# SCH_BI_PLANE__QLC_CONNECTOR_QLC260R__22_.net
KiCad netlist of a schematic drawn in EasyEDA
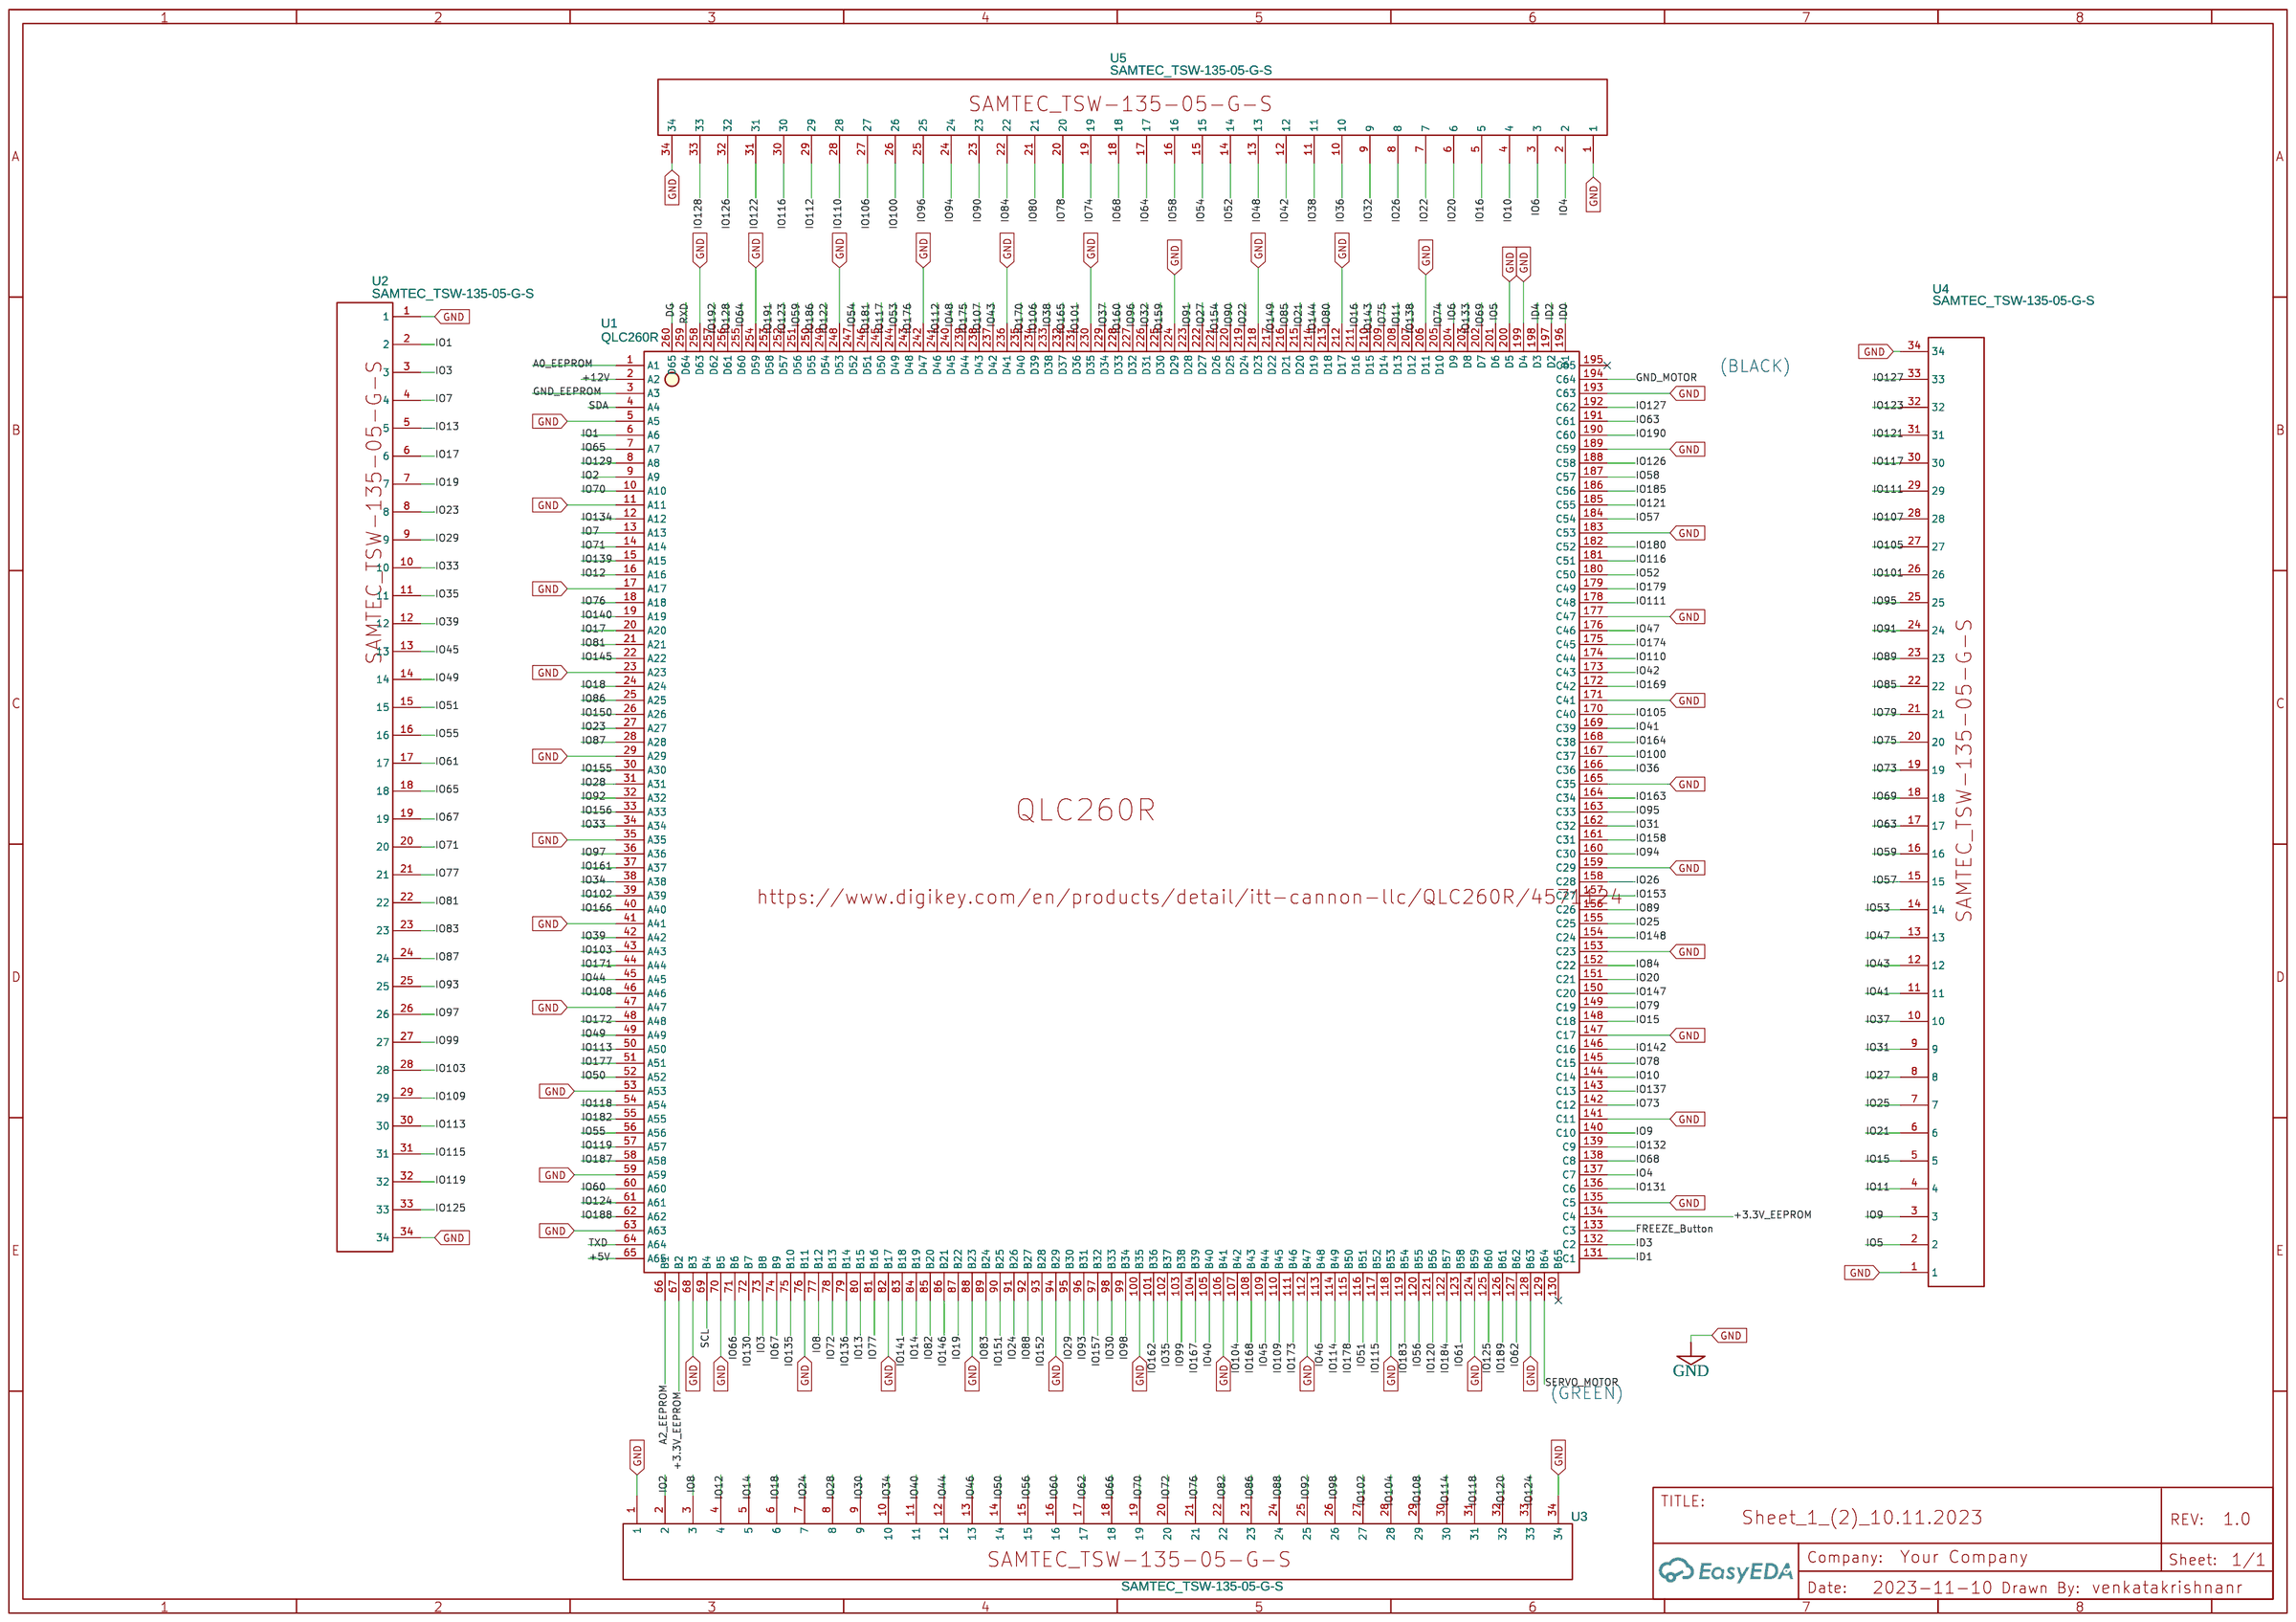
[diagram p0: schematic sheet]

(export (version "E")
  (design (tool "Eeschema 10.0.6"))
  (components
    (comp (ref "U1")
      (value "QLC260R")
      (fields (field (name "Manufacturer") "ITT Cannon, LLC"))
      (libsource (lib "") (part "QLC260R"))
    )
    (comp (ref "U2")
      (value "SAMTEC_TSW-135-05-G-S")
      (fields (field (name "Manufacturer Part") "TSW-135-05-G-S") (field (name "Manufacturer") "Samtec Inc."))
      (libsource (lib "") (part "SAMTEC_TSW-135-05-G-S_1"))
    )
    (comp (ref "U3")
      (value "SAMTEC_TSW-135-05-G-S")
      (fields (field (name "Manufacturer Part") "TSW-135-05-G-S") (field (name "Manufacturer") "Samtec Inc."))
      (libsource (lib "") (part "SAMTEC_TSW-135-05-G-S_3"))
    )
    (comp (ref "U4")
      (value "SAMTEC_TSW-135-05-G-S")
      (fields (field (name "Manufacturer Part") "TSW-135-05-G-S") (field (name "Manufacturer") "Samtec Inc."))
      (libsource (lib "") (part "SAMTEC_TSW-135-05-G-S_2"))
    )
    (comp (ref "U5")
      (value "SAMTEC_TSW-135-05-G-S")
      (fields (field (name "Manufacturer Part") "TSW-135-05-G-S") (field (name "Manufacturer") "Samtec Inc."))
      (libsource (lib "") (part "SAMTEC_TSW-135-05-G-S"))
    )
  )
  (nets
    (net (code "1") (name "/+3.3V_EEPROM") (class "Default")
      (node (ref "U1") (pin "134") (pinfunction "C4_134") (pintype "unspecified"))
      (node (ref "U1") (pin "67") (pinfunction "B2_67") (pintype "unspecified"))
    )
    (net (code "2") (name "/+5V") (class "Default")
      (node (ref "U1") (pin "65") (pinfunction "A65_65") (pintype "unspecified"))
    )
    (net (code "3") (name "/+12V") (class "Default")
      (node (ref "U1") (pin "2") (pinfunction "A2_2") (pintype "unspecified"))
    )
    (net (code "4") (name "/A0_EEPROM") (class "Default")
      (node (ref "U1") (pin "1") (pinfunction "A1_1") (pintype "unspecified"))
    )
    (net (code "5") (name "/A2_EEPROM") (class "Default")
      (node (ref "U1") (pin "66") (pinfunction "B1_66") (pintype "unspecified"))
    )
    (net (code "6") (name "/DG") (class "Default")
      (node (ref "U1") (pin "260") (pinfunction "D65_260") (pintype "unspecified"))
    )
    (net (code "7") (name "/FREEZE_Button") (class "Default")
      (node (ref "U1") (pin "133") (pinfunction "C3_133") (pintype "unspecified"))
    )
    (net (code "8") (name "/GND_EEPROM") (class "Default")
      (node (ref "U1") (pin "3") (pinfunction "A3_3") (pintype "unspecified"))
    )
    (net (code "9") (name "/GND_MOTOR") (class "Default")
      (node (ref "U1") (pin "194") (pinfunction "C64_194") (pintype "unspecified"))
    )
    (net (code "10") (name "/ID0") (class "Default")
      (node (ref "U1") (pin "196") (pinfunction "D1_196") (pintype "unspecified"))
    )
    (net (code "11") (name "/ID1") (class "Default")
      (node (ref "U1") (pin "131") (pinfunction "C1_131") (pintype "unspecified"))
    )
    (net (code "12") (name "/ID2") (class "Default")
      (node (ref "U1") (pin "197") (pinfunction "D2_197") (pintype "unspecified"))
    )
    (net (code "13") (name "/ID3") (class "Default")
      (node (ref "U1") (pin "132") (pinfunction "C2_132") (pintype "unspecified"))
    )
    (net (code "14") (name "/ID4") (class "Default")
      (node (ref "U1") (pin "198") (pinfunction "D3_198") (pintype "unspecified"))
    )
    (net (code "15") (name "/IO1") (class "Default")
      (node (ref "U1") (pin "6") (pinfunction "A6_6") (pintype "unspecified"))
      (node (ref "U2") (pin "2") (pinfunction "2_2") (pintype "unspecified"))
    )
    (net (code "16") (name "/IO2") (class "Default")
      (node (ref "U1") (pin "9") (pinfunction "A9_9") (pintype "unspecified"))
      (node (ref "U3") (pin "2") (pinfunction "2_2") (pintype "unspecified"))
    )
    (net (code "17") (name "/IO3") (class "Default")
      (node (ref "U1") (pin "73") (pinfunction "B8_73") (pintype "unspecified"))
      (node (ref "U2") (pin "3") (pinfunction "3_3") (pintype "unspecified"))
    )
    (net (code "18") (name "/IO4") (class "Default")
      (node (ref "U1") (pin "137") (pinfunction "C7_137") (pintype "unspecified"))
      (node (ref "U5") (pin "2") (pinfunction "2_2") (pintype "unspecified"))
    )
    (net (code "19") (name "/IO5") (class "Default")
      (node (ref "U1") (pin "201") (pinfunction "D6_201") (pintype "unspecified"))
      (node (ref "U4") (pin "2") (pinfunction "2_2") (pintype "unspecified"))
    )
    (net (code "20") (name "/IO6") (class "Default")
      (node (ref "U1") (pin "204") (pinfunction "D9_204") (pintype "unspecified"))
      (node (ref "U5") (pin "3") (pinfunction "3_3") (pintype "unspecified"))
    )
    (net (code "21") (name "/IO7") (class "Default")
      (node (ref "U1") (pin "13") (pinfunction "A13_13") (pintype "unspecified"))
      (node (ref "U2") (pin "4") (pinfunction "4_4") (pintype "unspecified"))
    )
    (net (code "22") (name "/IO8") (class "Default")
      (node (ref "U1") (pin "77") (pinfunction "B12_77") (pintype "unspecified"))
      (node (ref "U3") (pin "3") (pinfunction "3_3") (pintype "unspecified"))
    )
    (net (code "23") (name "/IO9") (class "Default")
      (node (ref "U1") (pin "140") (pinfunction "C10_140") (pintype "unspecified"))
      (node (ref "U4") (pin "3") (pinfunction "3_3") (pintype "unspecified"))
    )
    (net (code "24") (name "/IO10") (class "Default")
      (node (ref "U1") (pin "144") (pinfunction "C14_144") (pintype "unspecified"))
      (node (ref "U5") (pin "4") (pinfunction "4_4") (pintype "unspecified"))
    )
    (net (code "25") (name "/IO11") (class "Default")
      (node (ref "U1") (pin "208") (pinfunction "D13_208") (pintype "unspecified"))
      (node (ref "U4") (pin "4") (pinfunction "4_4") (pintype "unspecified"))
    )
    (net (code "26") (name "/IO12") (class "Default")
      (node (ref "U1") (pin "16") (pinfunction "A16_16") (pintype "unspecified"))
      (node (ref "U3") (pin "4") (pinfunction "4_4") (pintype "unspecified"))
    )
    (net (code "27") (name "/IO13") (class "Default")
      (node (ref "U1") (pin "80") (pinfunction "B15_80") (pintype "unspecified"))
      (node (ref "U2") (pin "5") (pinfunction "5_5") (pintype "unspecified"))
    )
    (net (code "28") (name "/IO14") (class "Default")
      (node (ref "U1") (pin "84") (pinfunction "B19_84") (pintype "unspecified"))
      (node (ref "U3") (pin "5") (pinfunction "5_5") (pintype "unspecified"))
    )
    (net (code "29") (name "/IO15") (class "Default")
      (node (ref "U1") (pin "148") (pinfunction "C18_148") (pintype "unspecified"))
      (node (ref "U4") (pin "5") (pinfunction "5_5") (pintype "unspecified"))
    )
    (net (code "30") (name "/IO16") (class "Default")
      (node (ref "U1") (pin "211") (pinfunction "D16_211") (pintype "unspecified"))
      (node (ref "U5") (pin "5") (pinfunction "5_5") (pintype "unspecified"))
    )
    (net (code "31") (name "/IO17") (class "Default")
      (node (ref "U1") (pin "20") (pinfunction "A20_20") (pintype "unspecified"))
      (node (ref "U2") (pin "6") (pinfunction "6_6") (pintype "unspecified"))
    )
    (net (code "32") (name "/IO18") (class "Default")
      (node (ref "U1") (pin "24") (pinfunction "A24_24") (pintype "unspecified"))
      (node (ref "U3") (pin "6") (pinfunction "6_6") (pintype "unspecified"))
    )
    (net (code "33") (name "/IO19") (class "Default")
      (node (ref "U1") (pin "87") (pinfunction "B22_87") (pintype "unspecified"))
      (node (ref "U2") (pin "7") (pinfunction "7_7") (pintype "unspecified"))
    )
    (net (code "34") (name "/IO20") (class "Default")
      (node (ref "U1") (pin "151") (pinfunction "C21_151") (pintype "unspecified"))
      (node (ref "U5") (pin "6") (pinfunction "6_6") (pintype "unspecified"))
    )
    (net (code "35") (name "/IO21") (class "Default")
      (node (ref "U1") (pin "215") (pinfunction "D20_215") (pintype "unspecified"))
      (node (ref "U4") (pin "6") (pinfunction "6_6") (pintype "unspecified"))
    )
    (net (code "36") (name "/IO22") (class "Default")
      (node (ref "U1") (pin "219") (pinfunction "D24_219") (pintype "unspecified"))
      (node (ref "U5") (pin "7") (pinfunction "7_7") (pintype "unspecified"))
    )
    (net (code "37") (name "/IO23") (class "Default")
      (node (ref "U1") (pin "27") (pinfunction "A27_27") (pintype "unspecified"))
      (node (ref "U2") (pin "8") (pinfunction "8_8") (pintype "unspecified"))
    )
    (net (code "38") (name "/IO24") (class "Default")
      (node (ref "U1") (pin "91") (pinfunction "B26_91") (pintype "unspecified"))
      (node (ref "U3") (pin "7") (pinfunction "7_7") (pintype "unspecified"))
    )
    (net (code "39") (name "/IO25") (class "Default")
      (node (ref "U1") (pin "155") (pinfunction "C25_155") (pintype "unspecified"))
      (node (ref "U4") (pin "7") (pinfunction "7_7") (pintype "unspecified"))
    )
    (net (code "40") (name "/IO26") (class "Default")
      (node (ref "U1") (pin "158") (pinfunction "C28_158") (pintype "unspecified"))
      (node (ref "U5") (pin "8") (pinfunction "8_8") (pintype "unspecified"))
    )
    (net (code "41") (name "/IO27") (class "Default")
      (node (ref "U1") (pin "222") (pinfunction "D27_222") (pintype "unspecified"))
      (node (ref "U4") (pin "8") (pinfunction "8_8") (pintype "unspecified"))
    )
    (net (code "42") (name "/IO28") (class "Default")
      (node (ref "U1") (pin "31") (pinfunction "A31_31") (pintype "unspecified"))
      (node (ref "U3") (pin "8") (pinfunction "8_8") (pintype "unspecified"))
    )
    (net (code "43") (name "/IO29") (class "Default")
      (node (ref "U1") (pin "95") (pinfunction "B30_95") (pintype "unspecified"))
      (node (ref "U2") (pin "9") (pinfunction "9_9") (pintype "unspecified"))
    )
    (net (code "44") (name "/IO30") (class "Default")
      (node (ref "U1") (pin "98") (pinfunction "B33_98") (pintype "unspecified"))
      (node (ref "U3") (pin "9") (pinfunction "9_9") (pintype "unspecified"))
    )
    (net (code "45") (name "/IO31") (class "Default")
      (node (ref "U1") (pin "162") (pinfunction "C32_162") (pintype "unspecified"))
      (node (ref "U4") (pin "9") (pinfunction "9_9") (pintype "unspecified"))
    )
    (net (code "46") (name "/IO32") (class "Default")
      (node (ref "U1") (pin "226") (pinfunction "D31_226") (pintype "unspecified"))
      (node (ref "U5") (pin "9") (pinfunction "9_9") (pintype "unspecified"))
    )
    (net (code "47") (name "/IO33") (class "Default")
      (node (ref "U1") (pin "34") (pinfunction "A34_34") (pintype "unspecified"))
      (node (ref "U2") (pin "10") (pinfunction "10_10") (pintype "unspecified"))
    )
    (net (code "48") (name "/IO34") (class "Default")
      (node (ref "U1") (pin "38") (pinfunction "A38_38") (pintype "unspecified"))
      (node (ref "U3") (pin "10") (pinfunction "10_10") (pintype "unspecified"))
    )
    (net (code "49") (name "/IO35") (class "Default")
      (node (ref "U1") (pin "102") (pinfunction "B37_102") (pintype "unspecified"))
      (node (ref "U2") (pin "11") (pinfunction "11_11") (pintype "unspecified"))
    )
    (net (code "50") (name "/IO36") (class "Default")
      (node (ref "U1") (pin "166") (pinfunction "C36_166") (pintype "unspecified"))
      (node (ref "U5") (pin "10") (pinfunction "10_10") (pintype "unspecified"))
    )
    (net (code "51") (name "/IO37") (class "Default")
      (node (ref "U1") (pin "229") (pinfunction "D34_229") (pintype "unspecified"))
      (node (ref "U4") (pin "10") (pinfunction "10_10") (pintype "unspecified"))
    )
    (net (code "52") (name "/IO38") (class "Default")
      (node (ref "U1") (pin "233") (pinfunction "D38_233") (pintype "unspecified"))
      (node (ref "U5") (pin "11") (pinfunction "11_11") (pintype "unspecified"))
    )
    (net (code "53") (name "/IO39") (class "Default")
      (node (ref "U1") (pin "42") (pinfunction "A42_42") (pintype "unspecified"))
      (node (ref "U2") (pin "12") (pinfunction "12_12") (pintype "unspecified"))
    )
    (net (code "54") (name "/IO40") (class "Default")
      (node (ref "U1") (pin "105") (pinfunction "B40_105") (pintype "unspecified"))
      (node (ref "U3") (pin "11") (pinfunction "11_11") (pintype "unspecified"))
    )
    (net (code "55") (name "/IO41") (class "Default")
      (node (ref "U1") (pin "169") (pinfunction "C39_169") (pintype "unspecified"))
      (node (ref "U4") (pin "11") (pinfunction "11_11") (pintype "unspecified"))
    )
    (net (code "56") (name "/IO42") (class "Default")
      (node (ref "U1") (pin "173") (pinfunction "C43_173") (pintype "unspecified"))
      (node (ref "U5") (pin "12") (pinfunction "12_12") (pintype "unspecified"))
    )
    (net (code "57") (name "/IO43") (class "Default")
      (node (ref "U1") (pin "237") (pinfunction "D42_237") (pintype "unspecified"))
      (node (ref "U4") (pin "12") (pinfunction "12_12") (pintype "unspecified"))
    )
    (net (code "58") (name "/IO44") (class "Default")
      (node (ref "U1") (pin "45") (pinfunction "A45_45") (pintype "unspecified"))
      (node (ref "U3") (pin "12") (pinfunction "12_12") (pintype "unspecified"))
    )
    (net (code "59") (name "/IO45") (class "Default")
      (node (ref "U1") (pin "109") (pinfunction "B44_109") (pintype "unspecified"))
      (node (ref "U2") (pin "13") (pinfunction "13_13") (pintype "unspecified"))
    )
    (net (code "60") (name "/IO46") (class "Default")
      (node (ref "U1") (pin "113") (pinfunction "B48_113") (pintype "unspecified"))
      (node (ref "U3") (pin "13") (pinfunction "13_13") (pintype "unspecified"))
    )
    (net (code "61") (name "/IO47") (class "Default")
      (node (ref "U1") (pin "176") (pinfunction "C46_176") (pintype "unspecified"))
      (node (ref "U4") (pin "13") (pinfunction "13_13") (pintype "unspecified"))
    )
    (net (code "62") (name "/IO48") (class "Default")
      (node (ref "U1") (pin "240") (pinfunction "D45_240") (pintype "unspecified"))
      (node (ref "U5") (pin "13") (pinfunction "13_13") (pintype "unspecified"))
    )
    (net (code "63") (name "/IO49") (class "Default")
      (node (ref "U1") (pin "49") (pinfunction "A49_49") (pintype "unspecified"))
      (node (ref "U2") (pin "14") (pinfunction "14_14") (pintype "unspecified"))
    )
    (net (code "64") (name "/IO50") (class "Default")
      (node (ref "U1") (pin "52") (pinfunction "A52_52") (pintype "unspecified"))
      (node (ref "U3") (pin "14") (pinfunction "14_14") (pintype "unspecified"))
    )
    (net (code "65") (name "/IO51") (class "Default")
      (node (ref "U1") (pin "116") (pinfunction "B51_116") (pintype "unspecified"))
      (node (ref "U2") (pin "15") (pinfunction "15_15") (pintype "unspecified"))
    )
    (net (code "66") (name "/IO52") (class "Default")
      (node (ref "U1") (pin "180") (pinfunction "C50_180") (pintype "unspecified"))
      (node (ref "U5") (pin "14") (pinfunction "14_14") (pintype "unspecified"))
    )
    (net (code "67") (name "/IO53") (class "Default")
      (node (ref "U1") (pin "244") (pinfunction "D49_244") (pintype "unspecified"))
      (node (ref "U4") (pin "14") (pinfunction "14_14") (pintype "unspecified"))
    )
    (net (code "68") (name "/IO54") (class "Default")
      (node (ref "U1") (pin "247") (pinfunction "D52_247") (pintype "unspecified"))
      (node (ref "U5") (pin "15") (pinfunction "15_15") (pintype "unspecified"))
    )
    (net (code "69") (name "/IO55") (class "Default")
      (node (ref "U1") (pin "56") (pinfunction "A56_56") (pintype "unspecified"))
      (node (ref "U2") (pin "16") (pinfunction "16_16") (pintype "unspecified"))
    )
    (net (code "70") (name "/IO56") (class "Default")
      (node (ref "U1") (pin "120") (pinfunction "B55_120") (pintype "unspecified"))
      (node (ref "U3") (pin "15") (pinfunction "15_15") (pintype "unspecified"))
    )
    (net (code "71") (name "/IO57") (class "Default")
      (node (ref "U1") (pin "184") (pinfunction "C54_184") (pintype "unspecified"))
      (node (ref "U4") (pin "15") (pinfunction "15_15") (pintype "unspecified"))
    )
    (net (code "72") (name "/IO58") (class "Default")
      (node (ref "U1") (pin "187") (pinfunction "C57_187") (pintype "unspecified"))
      (node (ref "U5") (pin "16") (pinfunction "16_16") (pintype "unspecified"))
    )
    (net (code "73") (name "/IO59") (class "Default")
      (node (ref "U1") (pin "251") (pinfunction "D56_251") (pintype "unspecified"))
      (node (ref "U4") (pin "16") (pinfunction "16_16") (pintype "unspecified"))
    )
    (net (code "74") (name "/IO60") (class "Default")
      (node (ref "U1") (pin "60") (pinfunction "A60_60") (pintype "unspecified"))
      (node (ref "U3") (pin "16") (pinfunction "16_16") (pintype "unspecified"))
    )
    (net (code "75") (name "/IO61") (class "Default")
      (node (ref "U1") (pin "123") (pinfunction "B58_123") (pintype "unspecified"))
      (node (ref "U2") (pin "17") (pinfunction "17_17") (pintype "unspecified"))
    )
    (net (code "76") (name "/IO62") (class "Default")
      (node (ref "U1") (pin "127") (pinfunction "B62_127") (pintype "unspecified"))
      (node (ref "U3") (pin "17") (pinfunction "17_17") (pintype "unspecified"))
    )
    (net (code "77") (name "/IO63") (class "Default")
      (node (ref "U1") (pin "191") (pinfunction "C61_191") (pintype "unspecified"))
      (node (ref "U4") (pin "17") (pinfunction "17_17") (pintype "unspecified"))
    )
    (net (code "78") (name "/IO64") (class "Default")
      (node (ref "U1") (pin "255") (pinfunction "D60_255") (pintype "unspecified"))
      (node (ref "U5") (pin "17") (pinfunction "17_17") (pintype "unspecified"))
    )
    (net (code "79") (name "/IO65") (class "Default")
      (node (ref "U1") (pin "7") (pinfunction "A7_7") (pintype "unspecified"))
      (node (ref "U2") (pin "18") (pinfunction "18_18") (pintype "unspecified"))
    )
    (net (code "80") (name "/IO66") (class "Default")
      (node (ref "U1") (pin "71") (pinfunction "B6_71") (pintype "unspecified"))
      (node (ref "U3") (pin "18") (pinfunction "18_18") (pintype "unspecified"))
    )
    (net (code "81") (name "/IO67") (class "Default")
      (node (ref "U1") (pin "74") (pinfunction "B9_74") (pintype "unspecified"))
      (node (ref "U2") (pin "19") (pinfunction "19_19") (pintype "unspecified"))
    )
    (net (code "82") (name "/IO68") (class "Default")
      (node (ref "U1") (pin "138") (pinfunction "C8_138") (pintype "unspecified"))
      (node (ref "U5") (pin "18") (pinfunction "18_18") (pintype "unspecified"))
    )
    (net (code "83") (name "/IO69") (class "Default")
      (node (ref "U1") (pin "202") (pinfunction "D7_202") (pintype "unspecified"))
      (node (ref "U4") (pin "18") (pinfunction "18_18") (pintype "unspecified"))
    )
    (net (code "84") (name "/IO70") (class "Default")
      (node (ref "U1") (pin "10") (pinfunction "A10_10") (pintype "unspecified"))
      (node (ref "U3") (pin "19") (pinfunction "19_19") (pintype "unspecified"))
    )
    (net (code "85") (name "/IO71") (class "Default")
      (node (ref "U1") (pin "14") (pinfunction "A14_14") (pintype "unspecified"))
      (node (ref "U2") (pin "20") (pinfunction "20_20") (pintype "unspecified"))
    )
    (net (code "86") (name "/IO72") (class "Default")
      (node (ref "U1") (pin "78") (pinfunction "B13_78") (pintype "unspecified"))
      (node (ref "U3") (pin "20") (pinfunction "20_20") (pintype "unspecified"))
    )
    (net (code "87") (name "/IO73") (class "Default")
      (node (ref "U1") (pin "142") (pinfunction "C12_142") (pintype "unspecified"))
      (node (ref "U4") (pin "19") (pinfunction "19_19") (pintype "unspecified"))
    )
    (net (code "88") (name "/IO74") (class "Default")
      (node (ref "U1") (pin "205") (pinfunction "D10_205") (pintype "unspecified"))
      (node (ref "U5") (pin "19") (pinfunction "19_19") (pintype "unspecified"))
    )
    (net (code "89") (name "/IO75") (class "Default")
      (node (ref "U1") (pin "209") (pinfunction "D14_209") (pintype "unspecified"))
      (node (ref "U4") (pin "20") (pinfunction "20_20") (pintype "unspecified"))
    )
    (net (code "90") (name "/IO76") (class "Default")
      (node (ref "U1") (pin "18") (pinfunction "A18_18") (pintype "unspecified"))
      (node (ref "U3") (pin "21") (pinfunction "21_21") (pintype "unspecified"))
    )
    (net (code "91") (name "/IO77") (class "Default")
      (node (ref "U1") (pin "81") (pinfunction "B16_81") (pintype "unspecified"))
      (node (ref "U2") (pin "21") (pinfunction "21_21") (pintype "unspecified"))
    )
    (net (code "92") (name "/IO78") (class "Default")
      (node (ref "U1") (pin "145") (pinfunction "C15_145") (pintype "unspecified"))
      (node (ref "U5") (pin "20") (pinfunction "20_20") (pintype "unspecified"))
    )
    (net (code "93") (name "/IO79") (class "Default")
      (node (ref "U1") (pin "149") (pinfunction "C19_149") (pintype "unspecified"))
      (node (ref "U4") (pin "21") (pinfunction "21_21") (pintype "unspecified"))
    )
    (net (code "94") (name "/IO80") (class "Default")
      (node (ref "U1") (pin "213") (pinfunction "D18_213") (pintype "unspecified"))
      (node (ref "U5") (pin "21") (pinfunction "21_21") (pintype "unspecified"))
    )
    (net (code "95") (name "/IO81") (class "Default")
      (node (ref "U1") (pin "21") (pinfunction "A21_21") (pintype "unspecified"))
      (node (ref "U2") (pin "22") (pinfunction "22_22") (pintype "unspecified"))
    )
    (net (code "96") (name "/IO82") (class "Default")
      (node (ref "U1") (pin "85") (pinfunction "B20_85") (pintype "unspecified"))
      (node (ref "U3") (pin "22") (pinfunction "22_22") (pintype "unspecified"))
    )
    (net (code "97") (name "/IO83") (class "Default")
      (node (ref "U1") (pin "89") (pinfunction "B24_89") (pintype "unspecified"))
      (node (ref "U2") (pin "23") (pinfunction "23_23") (pintype "unspecified"))
    )
    (net (code "98") (name "/IO84") (class "Default")
      (node (ref "U1") (pin "152") (pinfunction "C22_152") (pintype "unspecified"))
      (node (ref "U5") (pin "22") (pinfunction "22_22") (pintype "unspecified"))
    )
    (net (code "99") (name "/IO85") (class "Default")
      (node (ref "U1") (pin "216") (pinfunction "D21_216") (pintype "unspecified"))
      (node (ref "U4") (pin "22") (pinfunction "22_22") (pintype "unspecified"))
    )
    (net (code "100") (name "/IO86") (class "Default")
      (node (ref "U1") (pin "25") (pinfunction "A25_25") (pintype "unspecified"))
      (node (ref "U3") (pin "23") (pinfunction "23_23") (pintype "unspecified"))
    )
    (net (code "101") (name "/IO87") (class "Default")
      (node (ref "U1") (pin "28") (pinfunction "A28_28") (pintype "unspecified"))
      (node (ref "U2") (pin "24") (pinfunction "24_24") (pintype "unspecified"))
    )
    (net (code "102") (name "/IO88") (class "Default")
      (node (ref "U1") (pin "92") (pinfunction "B27_92") (pintype "unspecified"))
      (node (ref "U3") (pin "24") (pinfunction "24_24") (pintype "unspecified"))
    )
    (net (code "103") (name "/IO89") (class "Default")
      (node (ref "U1") (pin "156") (pinfunction "C26_156") (pintype "unspecified"))
      (node (ref "U4") (pin "23") (pinfunction "23_23") (pintype "unspecified"))
    )
    (net (code "104") (name "/IO90") (class "Default")
      (node (ref "U1") (pin "220") (pinfunction "D25_220") (pintype "unspecified"))
      (node (ref "U5") (pin "23") (pinfunction "23_23") (pintype "unspecified"))
    )
    (net (code "105") (name "/IO91") (class "Default")
      (node (ref "U1") (pin "223") (pinfunction "D28_223") (pintype "unspecified"))
      (node (ref "U4") (pin "24") (pinfunction "24_24") (pintype "unspecified"))
    )
    (net (code "106") (name "/IO92") (class "Default")
      (node (ref "U1") (pin "32") (pinfunction "A32_32") (pintype "unspecified"))
      (node (ref "U3") (pin "25") (pinfunction "25_25") (pintype "unspecified"))
    )
    (net (code "107") (name "/IO93") (class "Default")
      (node (ref "U1") (pin "96") (pinfunction "B31_96") (pintype "unspecified"))
      (node (ref "U2") (pin "25") (pinfunction "25_25") (pintype "unspecified"))
    )
    (net (code "108") (name "/IO94") (class "Default")
      (node (ref "U1") (pin "160") (pinfunction "C30_160") (pintype "unspecified"))
      (node (ref "U5") (pin "24") (pinfunction "24_24") (pintype "unspecified"))
    )
    (net (code "109") (name "/IO95") (class "Default")
      (node (ref "U1") (pin "163") (pinfunction "C33_163") (pintype "unspecified"))
      (node (ref "U4") (pin "25") (pinfunction "25_25") (pintype "unspecified"))
    )
    (net (code "110") (name "/IO96") (class "Default")
      (node (ref "U1") (pin "227") (pinfunction "D32_227") (pintype "unspecified"))
      (node (ref "U5") (pin "25") (pinfunction "25_25") (pintype "unspecified"))
    )
    (net (code "111") (name "/IO97") (class "Default")
      (node (ref "U1") (pin "36") (pinfunction "A36_36") (pintype "unspecified"))
      (node (ref "U2") (pin "26") (pinfunction "26_26") (pintype "unspecified"))
    )
    (net (code "112") (name "/IO98") (class "Default")
      (node (ref "U1") (pin "99") (pinfunction "B34_99") (pintype "unspecified"))
      (node (ref "U3") (pin "26") (pinfunction "26_26") (pintype "unspecified"))
    )
    (net (code "113") (name "/IO99") (class "Default")
      (node (ref "U1") (pin "103") (pinfunction "B38_103") (pintype "unspecified"))
      (node (ref "U2") (pin "27") (pinfunction "27_27") (pintype "unspecified"))
    )
    (net (code "114") (name "/IO100") (class "Default")
      (node (ref "U1") (pin "167") (pinfunction "C37_167") (pintype "unspecified"))
      (node (ref "U5") (pin "26") (pinfunction "26_26") (pintype "unspecified"))
    )
    (net (code "115") (name "/IO101") (class "Default")
      (node (ref "U1") (pin "231") (pinfunction "D36_231") (pintype "unspecified"))
      (node (ref "U4") (pin "26") (pinfunction "26_26") (pintype "unspecified"))
    )
    (net (code "116") (name "/IO102") (class "Default")
      (node (ref "U1") (pin "39") (pinfunction "A39_39") (pintype "unspecified"))
      (node (ref "U3") (pin "27") (pinfunction "27_27") (pintype "unspecified"))
    )
    (net (code "117") (name "/IO103") (class "Default")
      (node (ref "U1") (pin "43") (pinfunction "A43_43") (pintype "unspecified"))
      (node (ref "U2") (pin "28") (pinfunction "28_28") (pintype "unspecified"))
    )
    (net (code "118") (name "/IO104") (class "Default")
      (node (ref "U1") (pin "107") (pinfunction "B42_107") (pintype "unspecified"))
      (node (ref "U3") (pin "28") (pinfunction "28_28") (pintype "unspecified"))
    )
    (net (code "119") (name "/IO105") (class "Default")
      (node (ref "U1") (pin "170") (pinfunction "C40_170") (pintype "unspecified"))
      (node (ref "U4") (pin "27") (pinfunction "27_27") (pintype "unspecified"))
    )
    (net (code "120") (name "/IO106") (class "Default")
      (node (ref "U1") (pin "234") (pinfunction "D39_234") (pintype "unspecified"))
      (node (ref "U5") (pin "27") (pinfunction "27_27") (pintype "unspecified"))
    )
    (net (code "121") (name "/IO107") (class "Default")
      (node (ref "U1") (pin "238") (pinfunction "D43_238") (pintype "unspecified"))
      (node (ref "U4") (pin "28") (pinfunction "28_28") (pintype "unspecified"))
    )
    (net (code "122") (name "/IO108") (class "Default")
      (node (ref "U1") (pin "46") (pinfunction "A46_46") (pintype "unspecified"))
      (node (ref "U3") (pin "29") (pinfunction "29_29") (pintype "unspecified"))
    )
    (net (code "123") (name "/IO109") (class "Default")
      (node (ref "U1") (pin "110") (pinfunction "B45_110") (pintype "unspecified"))
      (node (ref "U2") (pin "29") (pinfunction "29_29") (pintype "unspecified"))
    )
    (net (code "124") (name "/IO110") (class "Default")
      (node (ref "U1") (pin "174") (pinfunction "C44_174") (pintype "unspecified"))
      (node (ref "U5") (pin "28") (pinfunction "28_28") (pintype "unspecified"))
    )
    (net (code "125") (name "/IO111") (class "Default")
      (node (ref "U1") (pin "178") (pinfunction "C48_178") (pintype "unspecified"))
      (node (ref "U4") (pin "29") (pinfunction "29_29") (pintype "unspecified"))
    )
    (net (code "126") (name "/IO112") (class "Default")
      (node (ref "U1") (pin "241") (pinfunction "D46_241") (pintype "unspecified"))
      (node (ref "U5") (pin "29") (pinfunction "29_29") (pintype "unspecified"))
    )
    (net (code "127") (name "/IO113") (class "Default")
      (node (ref "U1") (pin "50") (pinfunction "A50_50") (pintype "unspecified"))
      (node (ref "U2") (pin "30") (pinfunction "30_30") (pintype "unspecified"))
    )
    (net (code "128") (name "/IO114") (class "Default")
      (node (ref "U1") (pin "114") (pinfunction "B49_114") (pintype "unspecified"))
      (node (ref "U3") (pin "30") (pinfunction "30_30") (pintype "unspecified"))
    )
    (net (code "129") (name "/IO115") (class "Default")
      (node (ref "U1") (pin "117") (pinfunction "B52_117") (pintype "unspecified"))
      (node (ref "U2") (pin "31") (pinfunction "31_31") (pintype "unspecified"))
    )
    (net (code "130") (name "/IO116") (class "Default")
      (node (ref "U1") (pin "181") (pinfunction "C51_181") (pintype "unspecified"))
      (node (ref "U5") (pin "30") (pinfunction "30_30") (pintype "unspecified"))
    )
    (net (code "131") (name "/IO117") (class "Default")
      (node (ref "U1") (pin "245") (pinfunction "D50_245") (pintype "unspecified"))
      (node (ref "U4") (pin "30") (pinfunction "30_30") (pintype "unspecified"))
    )
    (net (code "132") (name "/IO118") (class "Default")
      (node (ref "U1") (pin "54") (pinfunction "A54_54") (pintype "unspecified"))
      (node (ref "U3") (pin "31") (pinfunction "31_31") (pintype "unspecified"))
    )
    (net (code "133") (name "/IO119") (class "Default")
      (node (ref "U1") (pin "57") (pinfunction "A57_57") (pintype "unspecified"))
      (node (ref "U2") (pin "32") (pinfunction "32_32") (pintype "unspecified"))
    )
    (net (code "134") (name "/IO120") (class "Default")
      (node (ref "U1") (pin "121") (pinfunction "B56_121") (pintype "unspecified"))
      (node (ref "U3") (pin "32") (pinfunction "32_32") (pintype "unspecified"))
    )
    (net (code "135") (name "/IO121") (class "Default")
      (node (ref "U1") (pin "185") (pinfunction "C55_185") (pintype "unspecified"))
      (node (ref "U4") (pin "31") (pinfunction "31_31") (pintype "unspecified"))
    )
    (net (code "136") (name "/IO122") (class "Default")
      (node (ref "U1") (pin "249") (pinfunction "D54_249") (pintype "unspecified"))
      (node (ref "U5") (pin "31") (pinfunction "31_31") (pintype "unspecified"))
    )
    (net (code "137") (name "/IO123") (class "Default")
      (node (ref "U1") (pin "252") (pinfunction "D57_252") (pintype "unspecified"))
      (node (ref "U4") (pin "32") (pinfunction "32_32") (pintype "unspecified"))
    )
    (net (code "138") (name "/IO124") (class "Default")
      (node (ref "U1") (pin "61") (pinfunction "A61_61") (pintype "unspecified"))
      (node (ref "U3") (pin "33") (pinfunction "33_33") (pintype "unspecified"))
    )
    (net (code "139") (name "/IO125") (class "Default")
      (node (ref "U1") (pin "125") (pinfunction "B60_125") (pintype "unspecified"))
      (node (ref "U2") (pin "33") (pinfunction "33_33") (pintype "unspecified"))
    )
    (net (code "140") (name "/IO126") (class "Default")
      (node (ref "U1") (pin "188") (pinfunction "C58_188") (pintype "unspecified"))
      (node (ref "U5") (pin "32") (pinfunction "32_32") (pintype "unspecified"))
    )
    (net (code "141") (name "/IO127") (class "Default")
      (node (ref "U1") (pin "192") (pinfunction "C62_192") (pintype "unspecified"))
      (node (ref "U4") (pin "33") (pinfunction "33_33") (pintype "unspecified"))
    )
    (net (code "142") (name "/IO128") (class "Default")
      (node (ref "U1") (pin "256") (pinfunction "D61_256") (pintype "unspecified"))
      (node (ref "U5") (pin "33") (pinfunction "33_33") (pintype "unspecified"))
    )
    (net (code "143") (name "/IO129") (class "Default")
      (node (ref "U1") (pin "8") (pinfunction "A8_8") (pintype "unspecified"))
    )
    (net (code "144") (name "/IO130") (class "Default")
      (node (ref "U1") (pin "72") (pinfunction "B7_72") (pintype "unspecified"))
    )
    (net (code "145") (name "/IO131") (class "Default")
      (node (ref "U1") (pin "136") (pinfunction "C6_136") (pintype "unspecified"))
    )
    (net (code "146") (name "/IO132") (class "Default")
      (node (ref "U1") (pin "139") (pinfunction "C9_139") (pintype "unspecified"))
    )
    (net (code "147") (name "/IO133") (class "Default")
      (node (ref "U1") (pin "203") (pinfunction "D8_203") (pintype "unspecified"))
    )
    (net (code "148") (name "/IO134") (class "Default")
      (node (ref "U1") (pin "12") (pinfunction "A12_12") (pintype "unspecified"))
    )
    (net (code "149") (name "/IO135") (class "Default")
      (node (ref "U1") (pin "75") (pinfunction "B10_75") (pintype "unspecified"))
    )
    (net (code "150") (name "/IO136") (class "Default")
      (node (ref "U1") (pin "79") (pinfunction "B14_79") (pintype "unspecified"))
    )
    (net (code "151") (name "/IO137") (class "Default")
      (node (ref "U1") (pin "143") (pinfunction "C13_143") (pintype "unspecified"))
    )
    (net (code "152") (name "/IO138") (class "Default")
      (node (ref "U1") (pin "207") (pinfunction "D12_207") (pintype "unspecified"))
    )
    (net (code "153") (name "/IO139") (class "Default")
      (node (ref "U1") (pin "15") (pinfunction "A15_15") (pintype "unspecified"))
    )
    (net (code "154") (name "/IO140") (class "Default")
      (node (ref "U1") (pin "19") (pinfunction "A19_19") (pintype "unspecified"))
    )
    (net (code "155") (name "/IO141") (class "Default")
      (node (ref "U1") (pin "83") (pinfunction "B18_83") (pintype "unspecified"))
    )
    (net (code "156") (name "/IO142") (class "Default")
      (node (ref "U1") (pin "146") (pinfunction "C16_146") (pintype "unspecified"))
    )
    (net (code "157") (name "/IO143") (class "Default")
      (node (ref "U1") (pin "210") (pinfunction "D15_210") (pintype "unspecified"))
    )
    (net (code "158") (name "/IO144") (class "Default")
      (node (ref "U1") (pin "214") (pinfunction "D19_214") (pintype "unspecified"))
    )
    (net (code "159") (name "/IO145") (class "Default")
      (node (ref "U1") (pin "22") (pinfunction "A22_22") (pintype "unspecified"))
    )
    (net (code "160") (name "/IO146") (class "Default")
      (node (ref "U1") (pin "86") (pinfunction "B21_86") (pintype "unspecified"))
    )
    (net (code "161") (name "/IO147") (class "Default")
      (node (ref "U1") (pin "150") (pinfunction "C20_150") (pintype "unspecified"))
    )
    (net (code "162") (name "/IO148") (class "Default")
      (node (ref "U1") (pin "154") (pinfunction "C24_154") (pintype "unspecified"))
    )
    (net (code "163") (name "/IO149") (class "Default")
      (node (ref "U1") (pin "217") (pinfunction "D22_217") (pintype "unspecified"))
    )
    (net (code "164") (name "/IO150") (class "Default")
      (node (ref "U1") (pin "26") (pinfunction "A26_26") (pintype "unspecified"))
    )
    (net (code "165") (name "/IO151") (class "Default")
      (node (ref "U1") (pin "90") (pinfunction "B25_90") (pintype "unspecified"))
    )
    (net (code "166") (name "/IO152") (class "Default")
      (node (ref "U1") (pin "93") (pinfunction "B28_93") (pintype "unspecified"))
    )
    (net (code "167") (name "/IO153") (class "Default")
      (node (ref "U1") (pin "157") (pinfunction "C27_157") (pintype "unspecified"))
    )
    (net (code "168") (name "/IO154") (class "Default")
      (node (ref "U1") (pin "221") (pinfunction "D26_221") (pintype "unspecified"))
    )
    (net (code "169") (name "/IO155") (class "Default")
      (node (ref "U1") (pin "30") (pinfunction "A30_30") (pintype "unspecified"))
    )
    (net (code "170") (name "/IO156") (class "Default")
      (node (ref "U1") (pin "33") (pinfunction "A33_33") (pintype "unspecified"))
    )
    (net (code "171") (name "/IO157") (class "Default")
      (node (ref "U1") (pin "97") (pinfunction "B32_97") (pintype "unspecified"))
    )
    (net (code "172") (name "/IO158") (class "Default")
      (node (ref "U1") (pin "161") (pinfunction "C31_161") (pintype "unspecified"))
    )
    (net (code "173") (name "/IO159") (class "Default")
      (node (ref "U1") (pin "225") (pinfunction "D30_225") (pintype "unspecified"))
    )
    (net (code "174") (name "/IO160") (class "Default")
      (node (ref "U1") (pin "228") (pinfunction "D33_228") (pintype "unspecified"))
    )
    (net (code "175") (name "/IO161") (class "Default")
      (node (ref "U1") (pin "37") (pinfunction "A37_37") (pintype "unspecified"))
    )
    (net (code "176") (name "/IO162") (class "Default")
      (node (ref "U1") (pin "101") (pinfunction "B36_101") (pintype "unspecified"))
    )
    (net (code "177") (name "/IO163") (class "Default")
      (node (ref "U1") (pin "164") (pinfunction "C34_164") (pintype "unspecified"))
    )
    (net (code "178") (name "/IO164") (class "Default")
      (node (ref "U1") (pin "168") (pinfunction "C38_168") (pintype "unspecified"))
    )
    (net (code "179") (name "/IO165") (class "Default")
      (node (ref "U1") (pin "232") (pinfunction "D37_232") (pintype "unspecified"))
    )
    (net (code "180") (name "/IO166") (class "Default")
      (node (ref "U1") (pin "40") (pinfunction "A40_40") (pintype "unspecified"))
    )
    (net (code "181") (name "/IO167") (class "Default")
      (node (ref "U1") (pin "104") (pinfunction "B39_104") (pintype "unspecified"))
    )
    (net (code "182") (name "/IO168") (class "Default")
      (node (ref "U1") (pin "108") (pinfunction "B43_108") (pintype "unspecified"))
    )
    (net (code "183") (name "/IO169") (class "Default")
      (node (ref "U1") (pin "172") (pinfunction "C42_172") (pintype "unspecified"))
    )
    (net (code "184") (name "/IO170") (class "Default")
      (node (ref "U1") (pin "235") (pinfunction "D40_235") (pintype "unspecified"))
    )
    (net (code "185") (name "/IO171") (class "Default")
      (node (ref "U1") (pin "44") (pinfunction "A44_44") (pintype "unspecified"))
    )
    (net (code "186") (name "/IO172") (class "Default")
      (node (ref "U1") (pin "48") (pinfunction "A48_48") (pintype "unspecified"))
    )
    (net (code "187") (name "/IO173") (class "Default")
      (node (ref "U1") (pin "111") (pinfunction "B46_111") (pintype "unspecified"))
    )
    (net (code "188") (name "/IO174") (class "Default")
      (node (ref "U1") (pin "175") (pinfunction "C45_175") (pintype "unspecified"))
    )
    (net (code "189") (name "/IO175") (class "Default")
      (node (ref "U1") (pin "239") (pinfunction "D44_239") (pintype "unspecified"))
    )
    (net (code "190") (name "/IO176") (class "Default")
      (node (ref "U1") (pin "243") (pinfunction "D48_243") (pintype "unspecified"))
    )
    (net (code "191") (name "/IO177") (class "Default")
      (node (ref "U1") (pin "51") (pinfunction "A51_51") (pintype "unspecified"))
    )
    (net (code "192") (name "/IO178") (class "Default")
      (node (ref "U1") (pin "115") (pinfunction "B50_115") (pintype "unspecified"))
    )
    (net (code "193") (name "/IO179") (class "Default")
      (node (ref "U1") (pin "179") (pinfunction "C49_179") (pintype "unspecified"))
    )
    (net (code "194") (name "/IO180") (class "Default")
      (node (ref "U1") (pin "182") (pinfunction "C52_182") (pintype "unspecified"))
    )
    (net (code "195") (name "/IO181") (class "Default")
      (node (ref "U1") (pin "246") (pinfunction "D51_246") (pintype "unspecified"))
    )
    (net (code "196") (name "/IO182") (class "Default")
      (node (ref "U1") (pin "55") (pinfunction "A55_55") (pintype "unspecified"))
    )
    (net (code "197") (name "/IO183") (class "Default")
      (node (ref "U1") (pin "119") (pinfunction "B54_119") (pintype "unspecified"))
    )
    (net (code "198") (name "/IO184") (class "Default")
      (node (ref "U1") (pin "122") (pinfunction "B57_122") (pintype "unspecified"))
    )
    (net (code "199") (name "/IO185") (class "Default")
      (node (ref "U1") (pin "186") (pinfunction "C56_186") (pintype "unspecified"))
    )
    (net (code "200") (name "/IO186") (class "Default")
      (node (ref "U1") (pin "250") (pinfunction "D55_250") (pintype "unspecified"))
    )
    (net (code "201") (name "/IO187") (class "Default")
      (node (ref "U1") (pin "58") (pinfunction "A58_58") (pintype "unspecified"))
    )
    (net (code "202") (name "/IO188") (class "Default")
      (node (ref "U1") (pin "62") (pinfunction "A62_62") (pintype "unspecified"))
    )
    (net (code "203") (name "/IO189") (class "Default")
      (node (ref "U1") (pin "126") (pinfunction "B61_126") (pintype "unspecified"))
    )
    (net (code "204") (name "/IO190") (class "Default")
      (node (ref "U1") (pin "190") (pinfunction "C60_190") (pintype "unspecified"))
    )
    (net (code "205") (name "/IO191") (class "Default")
      (node (ref "U1") (pin "253") (pinfunction "D58_253") (pintype "unspecified"))
    )
    (net (code "206") (name "/IO192") (class "Default")
      (node (ref "U1") (pin "257") (pinfunction "D62_257") (pintype "unspecified"))
    )
    (net (code "207") (name "/RXD") (class "Default")
      (node (ref "U1") (pin "259") (pinfunction "D64_259") (pintype "unspecified"))
    )
    (net (code "208") (name "/SCL") (class "Default")
      (node (ref "U1") (pin "69") (pinfunction "B4_69") (pintype "unspecified"))
    )
    (net (code "209") (name "/SDA") (class "Default")
      (node (ref "U1") (pin "4") (pinfunction "A4_4") (pintype "unspecified"))
    )
    (net (code "210") (name "/SERVO_MOTOR") (class "Default")
      (node (ref "U1") (pin "129") (pinfunction "B64_129") (pintype "unspecified"))
    )
    (net (code "211") (name "/TXD") (class "Default")
      (node (ref "U1") (pin "64") (pinfunction "A64_64") (pintype "unspecified"))
    )
    (net (code "212") (name "GND") (class "Default")
      (node (ref "U1") (pin "100") (pinfunction "B35_100") (pintype "unspecified"))
      (node (ref "U1") (pin "106") (pinfunction "B41_106") (pintype "unspecified"))
      (node (ref "U1") (pin "11") (pinfunction "A11_11") (pintype "unspecified"))
      (node (ref "U1") (pin "112") (pinfunction "B47_112") (pintype "unspecified"))
      (node (ref "U1") (pin "118") (pinfunction "B53_118") (pintype "unspecified"))
      (node (ref "U1") (pin "124") (pinfunction "B59_124") (pintype "unspecified"))
      (node (ref "U1") (pin "128") (pinfunction "B63_128") (pintype "unspecified"))
      (node (ref "U1") (pin "135") (pinfunction "C5_135") (pintype "unspecified"))
      (node (ref "U1") (pin "141") (pinfunction "C11_141") (pintype "unspecified"))
      (node (ref "U1") (pin "147") (pinfunction "C17_147") (pintype "unspecified"))
      (node (ref "U1") (pin "153") (pinfunction "C23_153") (pintype "unspecified"))
      (node (ref "U1") (pin "159") (pinfunction "C29_159") (pintype "unspecified"))
      (node (ref "U1") (pin "165") (pinfunction "C35_165") (pintype "unspecified"))
      (node (ref "U1") (pin "17") (pinfunction "A17_17") (pintype "unspecified"))
      (node (ref "U1") (pin "171") (pinfunction "C41_171") (pintype "unspecified"))
      (node (ref "U1") (pin "177") (pinfunction "C47_177") (pintype "unspecified"))
      (node (ref "U1") (pin "183") (pinfunction "C53_183") (pintype "unspecified"))
      (node (ref "U1") (pin "189") (pinfunction "C59_189") (pintype "unspecified"))
      (node (ref "U1") (pin "193") (pinfunction "C63_193") (pintype "unspecified"))
      (node (ref "U1") (pin "199") (pinfunction "D4_199") (pintype "unspecified"))
      (node (ref "U1") (pin "200") (pinfunction "D5_200") (pintype "unspecified"))
      (node (ref "U1") (pin "206") (pinfunction "D11_206") (pintype "unspecified"))
      (node (ref "U1") (pin "212") (pinfunction "D17_212") (pintype "unspecified"))
      (node (ref "U1") (pin "218") (pinfunction "D23_218") (pintype "unspecified"))
      (node (ref "U1") (pin "224") (pinfunction "D29_224") (pintype "unspecified"))
      (node (ref "U1") (pin "23") (pinfunction "A23_23") (pintype "unspecified"))
      (node (ref "U1") (pin "230") (pinfunction "D35_230") (pintype "unspecified"))
      (node (ref "U1") (pin "236") (pinfunction "D41_236") (pintype "unspecified"))
      (node (ref "U1") (pin "242") (pinfunction "D47_242") (pintype "unspecified"))
      (node (ref "U1") (pin "248") (pinfunction "D53_248") (pintype "unspecified"))
      (node (ref "U1") (pin "254") (pinfunction "D59_254") (pintype "unspecified"))
      (node (ref "U1") (pin "258") (pinfunction "D63_258") (pintype "unspecified"))
      (node (ref "U1") (pin "29") (pinfunction "A29_29") (pintype "unspecified"))
      (node (ref "U1") (pin "35") (pinfunction "A35_35") (pintype "unspecified"))
      (node (ref "U1") (pin "41") (pinfunction "A41_41") (pintype "unspecified"))
      (node (ref "U1") (pin "47") (pinfunction "A47_47") (pintype "unspecified"))
      (node (ref "U1") (pin "5") (pinfunction "A5_5") (pintype "unspecified"))
      (node (ref "U1") (pin "53") (pinfunction "A53_53") (pintype "unspecified"))
      (node (ref "U1") (pin "59") (pinfunction "A59_59") (pintype "unspecified"))
      (node (ref "U1") (pin "63") (pinfunction "A63_63") (pintype "unspecified"))
      (node (ref "U1") (pin "68") (pinfunction "B3_68") (pintype "unspecified"))
      (node (ref "U1") (pin "70") (pinfunction "B5_70") (pintype "unspecified"))
      (node (ref "U1") (pin "76") (pinfunction "B11_76") (pintype "unspecified"))
      (node (ref "U1") (pin "82") (pinfunction "B17_82") (pintype "unspecified"))
      (node (ref "U1") (pin "88") (pinfunction "B23_88") (pintype "unspecified"))
      (node (ref "U1") (pin "94") (pinfunction "B29_94") (pintype "unspecified"))
      (node (ref "U2") (pin "1") (pinfunction "1_1") (pintype "unspecified"))
      (node (ref "U2") (pin "34") (pinfunction "34_34") (pintype "unspecified"))
      (node (ref "U3") (pin "1") (pinfunction "1_1") (pintype "unspecified"))
      (node (ref "U3") (pin "34") (pinfunction "34_34") (pintype "unspecified"))
      (node (ref "U4") (pin "1") (pinfunction "1_1") (pintype "unspecified"))
      (node (ref "U4") (pin "34") (pinfunction "34_34") (pintype "unspecified"))
      (node (ref "U5") (pin "1") (pinfunction "1_1") (pintype "unspecified"))
      (node (ref "U5") (pin "34") (pinfunction "34_34") (pintype "unspecified"))
    )
    (net (code "213") (name "unconnected-(U1-B65-Pad130)") (class "Default")
      (node (ref "U1") (pin "130") (pinfunction "B65_130") (pintype "unspecified+no_connect"))
    )
    (net (code "214") (name "unconnected-(U1-C65-Pad195)") (class "Default")
      (node (ref "U1") (pin "195") (pinfunction "C65_195") (pintype "unspecified+no_connect"))
    )
  )
)
